# Printing2.net
KiCad netlist of a schematic drawn in Altium Designer
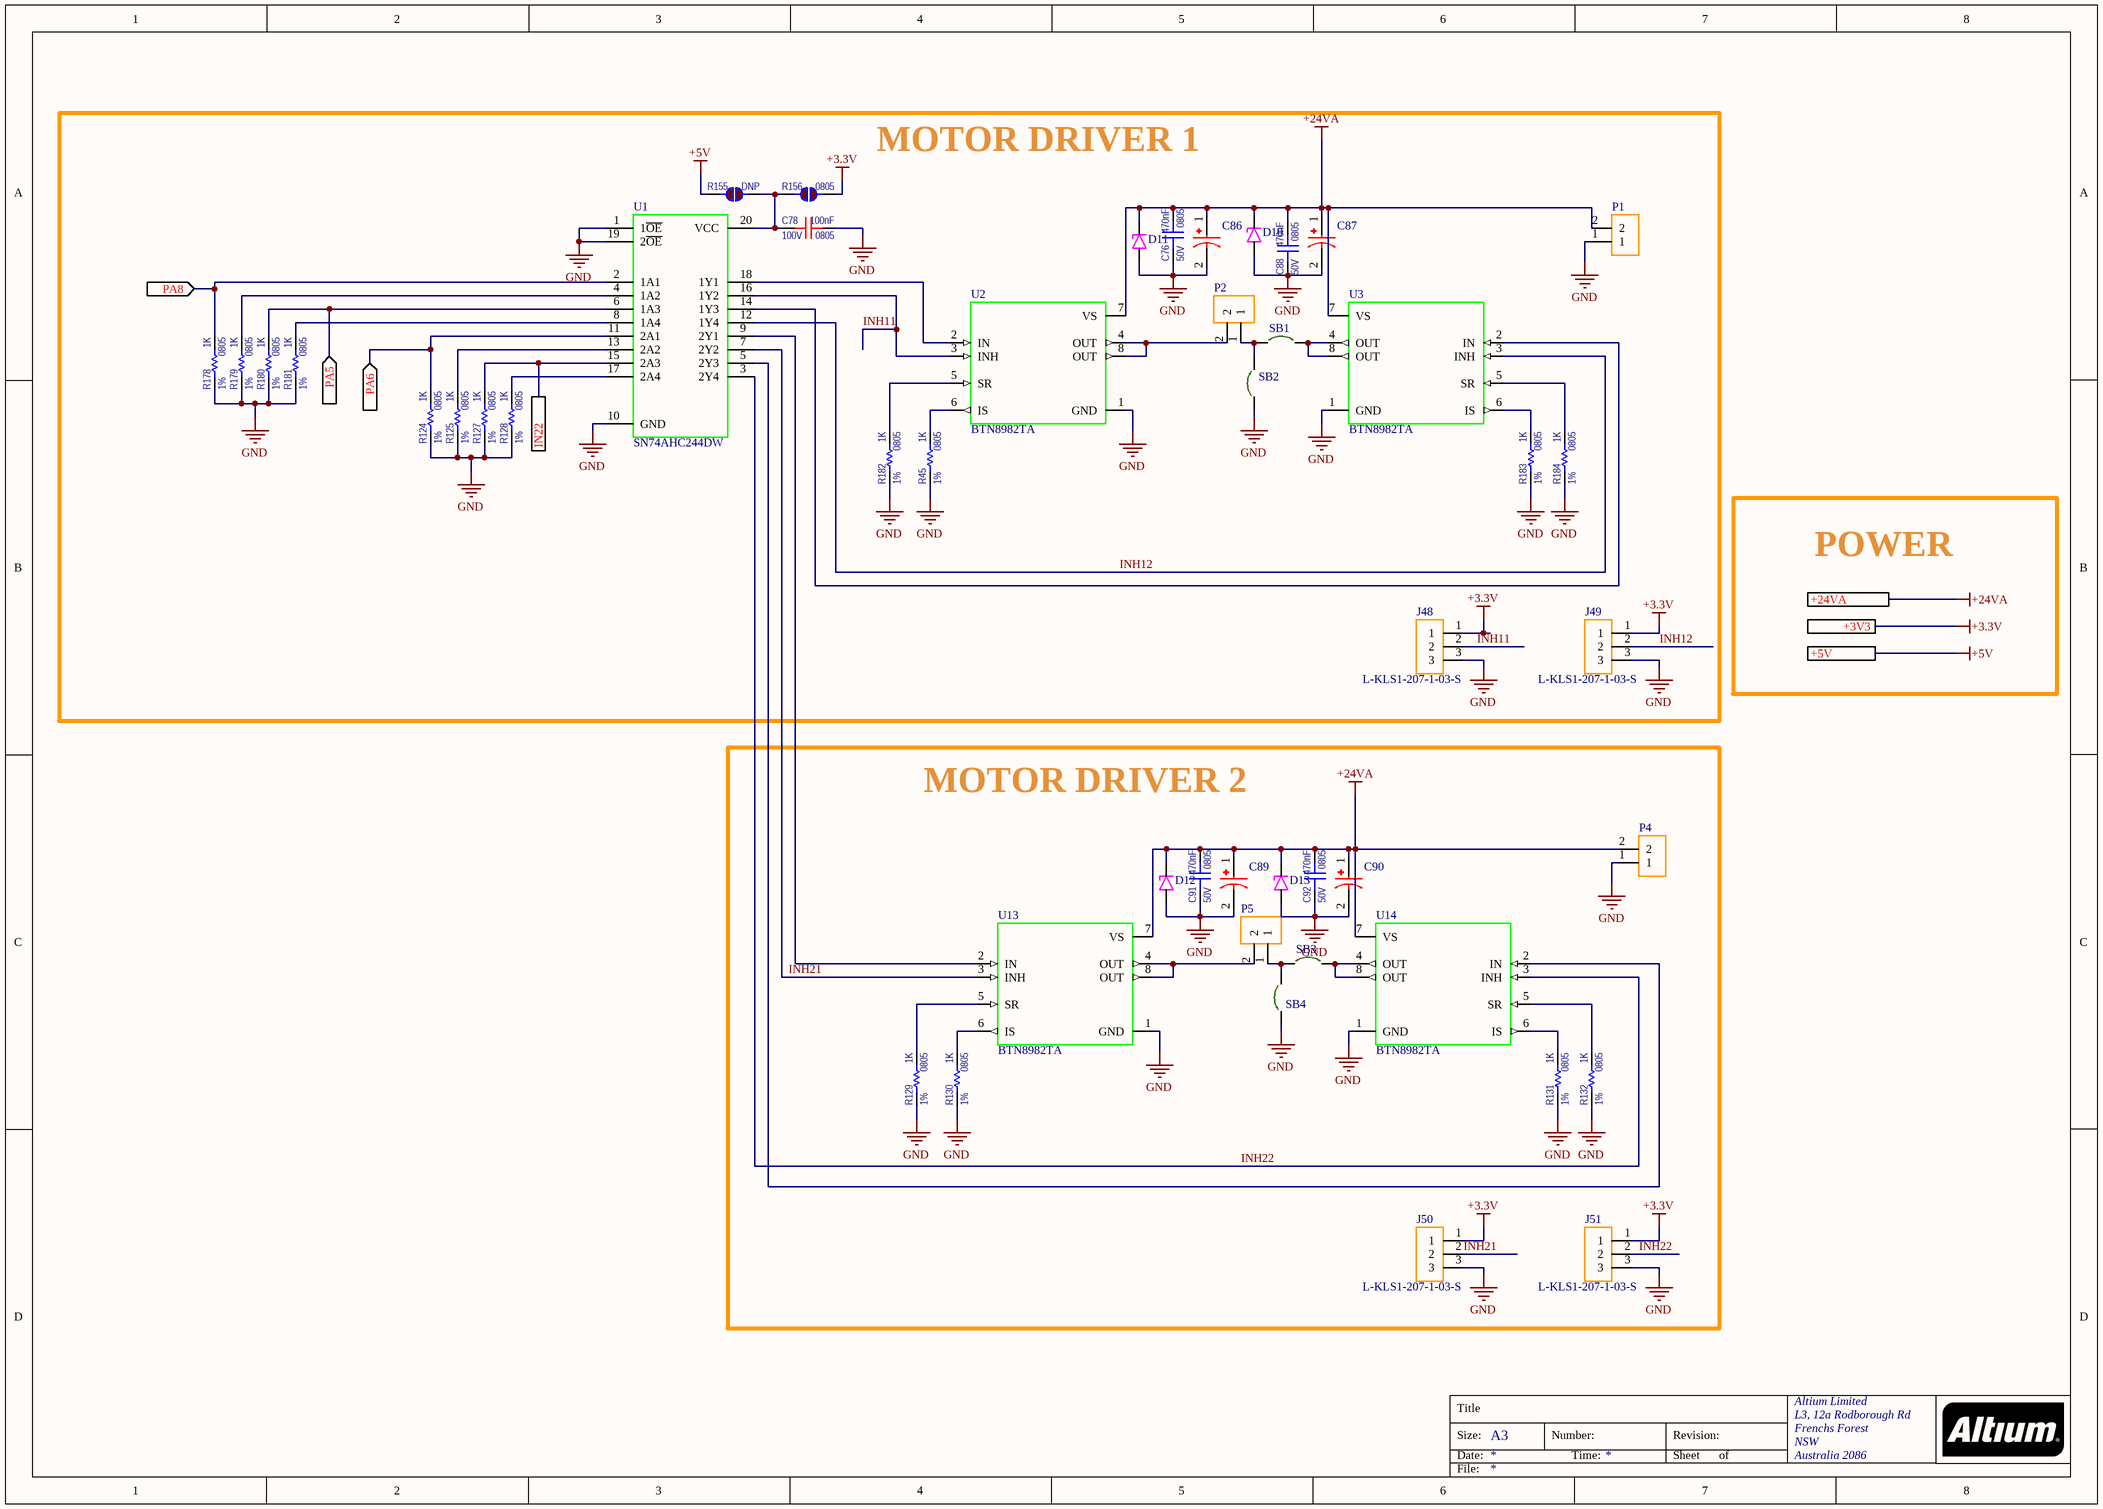
[diagram p0: Printing2.SchDoc]

(export (version "E")
  (design (tool "Eeschema 10.0.6"))
  (components
    (comp (ref "C76")
      (value "470nF")
      (footprint "C_0805_GEN_1.10H")
      (description "CAP_CER_470nF_50V_X7R_10%_0805")
      (fields
        (field (name "VOLTAGE") "50V")
        (field (name "PACKAGE") "0805")
        (field (name "SIMILAR PART") "CL21B474KBFVPNE")
        (field (name "TOLERANCE") "10%")
        (field (name "ADDED BY") "SonerI")
        (field (name "CHECKED BY") "İlkerU")
      )
      (libsource (lib "FireANTs_HwLibDB") (part "Capacitor"))
    )
    (comp (ref "C78")
      (value "100nF")
      (footprint "C_0805_GEN_1.40H")
      (description "CAP_CER_100nF_100V_X7R_10%_0805")
      (fields
        (field (name "VOLTAGE") "100V")
        (field (name "PACKAGE") "0805")
        (field (name "SIMILAR PART") "C0805C104J1RECAUTO7210; C0805X104J1RECAUTO")
        (field (name "TOLERANCE") "10%")
        (field (name "ADDED BY") "İlhanT")
        (field (name "CHECKED BY") "İlkerU")
      )
      (libsource (lib "FireANTs_HwLibDB") (part "ESDSafeCapacitor"))
    )
    (comp (ref "C86")
      (value "100uF/50V")
      (footprint "SC1V107M6L07KVR")
      (libsource (lib "Printing") (part "SC1V107M6L07KVR"))
    )
    (comp (ref "C87")
      (value "100uF/50V")
      (footprint "SC1V107M6L07KVR")
      (libsource (lib "Printing") (part "SC1V107M6L07KVR"))
    )
    (comp (ref "C88")
      (value "470nF")
      (footprint "C_0805_GEN_1.10H")
      (description "CAP_CER_470nF_50V_X7R_10%_0805")
      (fields
        (field (name "VOLTAGE") "50V")
        (field (name "PACKAGE") "0805")
        (field (name "SIMILAR PART") "CL21B474KBFVPNE")
        (field (name "TOLERANCE") "10%")
        (field (name "ADDED BY") "SonerI")
        (field (name "CHECKED BY") "İlkerU")
      )
      (libsource (lib "FireANTs_HwLibDB") (part "Capacitor"))
    )
    (comp (ref "C89")
      (value "100uF/50V")
      (footprint "SC1V107M6L07KVR")
      (libsource (lib "Printing") (part "SC1V107M6L07KVR"))
    )
    (comp (ref "C90")
      (value "100uF/50V")
      (footprint "SC1V107M6L07KVR")
      (libsource (lib "Printing") (part "SC1V107M6L07KVR"))
    )
    (comp (ref "C91")
      (value "470nF")
      (footprint "C_0805_GEN_1.10H")
      (description "CAP_CER_470nF_50V_X7R_10%_0805")
      (fields
        (field (name "VOLTAGE") "50V")
        (field (name "PACKAGE") "0805")
        (field (name "SIMILAR PART") "CL21B474KBFVPNE")
        (field (name "TOLERANCE") "10%")
        (field (name "ADDED BY") "SonerI")
        (field (name "CHECKED BY") "İlkerU")
      )
      (libsource (lib "FireANTs_HwLibDB") (part "Capacitor"))
    )
    (comp (ref "C92")
      (value "470nF")
      (footprint "C_0805_GEN_1.10H")
      (description "CAP_CER_470nF_50V_X7R_10%_0805")
      (fields
        (field (name "VOLTAGE") "50V")
        (field (name "PACKAGE") "0805")
        (field (name "SIMILAR PART") "CL21B474KBFVPNE")
        (field (name "TOLERANCE") "10%")
        (field (name "ADDED BY") "SonerI")
        (field (name "CHECKED BY") "İlkerU")
      )
      (libsource (lib "FireANTs_HwLibDB") (part "Capacitor"))
    )
    (comp (ref "D10")
      (value "SMBJ30A-E3/52")
      (footprint "S2G_R1_00001")
      (description "TVS DIODE 30VWM 48.4VC SMB")
      (fields (field (name "MANUFACTURER") "Vishay Semiconductors"))
      (libsource (lib "Printing") (part "SMBJ30A-E3/52"))
    )
    (comp (ref "D11")
      (value "SMBJ30A-E3/52")
      (footprint "S2G_R1_00001")
      (description "TVS DIODE 30VWM 48.4VC SMB")
      (fields (field (name "MANUFACTURER") "Vishay Semiconductors"))
      (libsource (lib "Printing") (part "SMBJ30A-E3/52"))
    )
    (comp (ref "D12")
      (value "SMBJ30A-E3/52")
      (footprint "S2G_R1_00001")
      (description "TVS DIODE 30VWM 48.4VC SMB")
      (fields (field (name "MANUFACTURER") "Vishay Semiconductors"))
      (libsource (lib "Printing") (part "SMBJ30A-E3/52"))
    )
    (comp (ref "D13")
      (value "SMBJ30A-E3/52")
      (footprint "S2G_R1_00001")
      (description "TVS DIODE 30VWM 48.4VC SMB")
      (fields (field (name "MANUFACTURER") "Vishay Semiconductors"))
      (libsource (lib "Printing") (part "SMBJ30A-E3/52"))
    )
    (comp (ref "J48")
      (value "L-KLS1-207-1-03-S")
      (footprint "L-KLS1-207-1-03-S")
      (libsource (lib "Printing") (part "L-KLS1-207-1-03-S"))
    )
    (comp (ref "J49")
      (value "L-KLS1-207-1-03-S")
      (footprint "L-KLS1-207-1-03-S")
      (libsource (lib "Printing") (part "L-KLS1-207-1-03-S"))
    )
    (comp (ref "J50")
      (value "L-KLS1-207-1-03-S")
      (footprint "L-KLS1-207-1-03-S")
      (libsource (lib "Printing") (part "L-KLS1-207-1-03-S"))
    )
    (comp (ref "J51")
      (value "L-KLS1-207-1-03-S")
      (footprint "L-KLS1-207-1-03-S")
      (libsource (lib "Printing") (part "L-KLS1-207-1-03-S"))
    )
    (comp (ref "P1")
      (value "5.08 Klemens")
      (footprint "5.08 Klemens")
      (libsource (lib "Printing") (part "5.08 Klemens"))
    )
    (comp (ref "P2")
      (value "5.08 Klemens")
      (footprint "5.08 Klemens")
      (libsource (lib "") (part "5.08 Klemens_1"))
    )
    (comp (ref "P4")
      (value "5.08 Klemens")
      (footprint "5.08 Klemens")
      (libsource (lib "Printing") (part "5.08 Klemens"))
    )
    (comp (ref "P5")
      (value "5.08 Klemens")
      (footprint "5.08 Klemens")
      (libsource (lib "") (part "5.08 Klemens_1"))
    )
    (comp (ref "R45")
      (value "1K")
      (footprint "R_0805_GEN_0.70H")
      (description "RES_STD_1K_0.125W_1%_100ppm_0805")
      (fields
        (field (name "TOLERANCE") "1%")
        (field (name "PACKAGE") "0805")
        (field (name "VOLTAGE") "150V")
        (field (name "Comment") "StandardResistor")
        (field (name "ADDED BY") "SonerI")
        (field (name "CHECKED BY") "YasinY")
      )
      (libsource (lib "FireANTs_HwLibDB") (part "StandardResistor"))
    )
    (comp (ref "R124")
      (value "1K")
      (footprint "R_0805_GEN_0.70H")
      (description "RES_STD_1K_0.125W_1%_100ppm_0805")
      (fields
        (field (name "TOLERANCE") "1%")
        (field (name "PACKAGE") "0805")
        (field (name "VOLTAGE") "150V")
        (field (name "Comment") "StandardResistor")
        (field (name "ADDED BY") "SonerI")
        (field (name "CHECKED BY") "YasinY")
      )
      (libsource (lib "FireANTs_HwLibDB") (part "StandardResistor"))
    )
    (comp (ref "R125")
      (value "1K")
      (footprint "R_0805_GEN_0.70H")
      (description "RES_STD_1K_0.125W_1%_100ppm_0805")
      (fields
        (field (name "TOLERANCE") "1%")
        (field (name "PACKAGE") "0805")
        (field (name "VOLTAGE") "150V")
        (field (name "Comment") "StandardResistor")
        (field (name "ADDED BY") "SonerI")
        (field (name "CHECKED BY") "YasinY")
      )
      (libsource (lib "FireANTs_HwLibDB") (part "StandardResistor"))
    )
    (comp (ref "R127")
      (value "1K")
      (footprint "R_0805_GEN_0.70H")
      (description "RES_STD_1K_0.125W_1%_100ppm_0805")
      (fields
        (field (name "TOLERANCE") "1%")
        (field (name "PACKAGE") "0805")
        (field (name "VOLTAGE") "150V")
        (field (name "Comment") "StandardResistor")
        (field (name "ADDED BY") "SonerI")
        (field (name "CHECKED BY") "YasinY")
      )
      (libsource (lib "FireANTs_HwLibDB") (part "StandardResistor"))
    )
    (comp (ref "R128")
      (value "1K")
      (footprint "R_0805_GEN_0.70H")
      (description "RES_STD_1K_0.125W_1%_100ppm_0805")
      (fields
        (field (name "TOLERANCE") "1%")
        (field (name "PACKAGE") "0805")
        (field (name "VOLTAGE") "150V")
        (field (name "Comment") "StandardResistor")
        (field (name "ADDED BY") "SonerI")
        (field (name "CHECKED BY") "YasinY")
      )
      (libsource (lib "FireANTs_HwLibDB") (part "StandardResistor"))
    )
    (comp (ref "R129")
      (value "1K")
      (footprint "R_0805_GEN_0.70H")
      (description "RES_STD_1K_0.125W_1%_100ppm_0805")
      (fields
        (field (name "TOLERANCE") "1%")
        (field (name "PACKAGE") "0805")
        (field (name "VOLTAGE") "150V")
        (field (name "Comment") "StandardResistor")
        (field (name "ADDED BY") "SonerI")
        (field (name "CHECKED BY") "YasinY")
      )
      (libsource (lib "FireANTs_HwLibDB") (part "StandardResistor"))
    )
    (comp (ref "R130")
      (value "1K")
      (footprint "R_0805_GEN_0.70H")
      (description "RES_STD_1K_0.125W_1%_100ppm_0805")
      (fields
        (field (name "TOLERANCE") "1%")
        (field (name "PACKAGE") "0805")
        (field (name "VOLTAGE") "150V")
        (field (name "Comment") "StandardResistor")
        (field (name "ADDED BY") "SonerI")
        (field (name "CHECKED BY") "YasinY")
      )
      (libsource (lib "FireANTs_HwLibDB") (part "StandardResistor"))
    )
    (comp (ref "R131")
      (value "1K")
      (footprint "R_0805_GEN_0.70H")
      (description "RES_STD_1K_0.125W_1%_100ppm_0805")
      (fields
        (field (name "TOLERANCE") "1%")
        (field (name "PACKAGE") "0805")
        (field (name "VOLTAGE") "150V")
        (field (name "Comment") "StandardResistor")
        (field (name "ADDED BY") "SonerI")
        (field (name "CHECKED BY") "YasinY")
      )
      (libsource (lib "FireANTs_HwLibDB") (part "StandardResistor"))
    )
    (comp (ref "R132")
      (value "1K")
      (footprint "R_0805_GEN_0.70H")
      (description "RES_STD_1K_0.125W_1%_100ppm_0805")
      (fields
        (field (name "TOLERANCE") "1%")
        (field (name "PACKAGE") "0805")
        (field (name "VOLTAGE") "150V")
        (field (name "Comment") "StandardResistor")
        (field (name "ADDED BY") "SonerI")
        (field (name "CHECKED BY") "YasinY")
      )
      (libsource (lib "FireANTs_HwLibDB") (part "StandardResistor"))
    )
    (comp (ref "R155")
      (value "StandardJumper")
      (footprint "R_0805_GEN_0.70H")
      (description "RES_STD_0R_0.125W_0805")
      (fields
        (field (name "PACKAGE") "DNP")
        (field (name "TOLERANCE") "5%")
        (field (name "VOLTAGE") "150V")
        (field (name "ADDED BY") "İlhanT")
        (field (name "CHECKED BY") "YasinY")
      )
      (libsource (lib "FireANTs_HwLibDB") (part "StandardJumper"))
    )
    (comp (ref "R156")
      (value "StandardJumper")
      (footprint "R_0805_GEN_0.70H")
      (description "RES_STD_0R_0.125W_0805")
      (fields
        (field (name "PACKAGE") "0805")
        (field (name "TOLERANCE") "5%")
        (field (name "VOLTAGE") "150V")
        (field (name "ADDED BY") "İlhanT")
        (field (name "CHECKED BY") "YasinY")
      )
      (libsource (lib "FireANTs_HwLibDB") (part "StandardJumper"))
    )
    (comp (ref "R178")
      (value "1K")
      (footprint "R_0805_GEN_0.70H")
      (description "RES_STD_1K_0.125W_1%_100ppm_0805")
      (fields
        (field (name "TOLERANCE") "1%")
        (field (name "PACKAGE") "0805")
        (field (name "VOLTAGE") "150V")
        (field (name "Comment") "StandardResistor")
        (field (name "ADDED BY") "SonerI")
        (field (name "CHECKED BY") "YasinY")
      )
      (libsource (lib "FireANTs_HwLibDB") (part "StandardResistor"))
    )
    (comp (ref "R179")
      (value "1K")
      (footprint "R_0805_GEN_0.70H")
      (description "RES_STD_1K_0.125W_1%_100ppm_0805")
      (fields
        (field (name "TOLERANCE") "1%")
        (field (name "PACKAGE") "0805")
        (field (name "VOLTAGE") "150V")
        (field (name "Comment") "StandardResistor")
        (field (name "ADDED BY") "SonerI")
        (field (name "CHECKED BY") "YasinY")
      )
      (libsource (lib "FireANTs_HwLibDB") (part "StandardResistor"))
    )
    (comp (ref "R180")
      (value "1K")
      (footprint "R_0805_GEN_0.70H")
      (description "RES_STD_1K_0.125W_1%_100ppm_0805")
      (fields
        (field (name "TOLERANCE") "1%")
        (field (name "PACKAGE") "0805")
        (field (name "VOLTAGE") "150V")
        (field (name "Comment") "StandardResistor")
        (field (name "ADDED BY") "SonerI")
        (field (name "CHECKED BY") "YasinY")
      )
      (libsource (lib "FireANTs_HwLibDB") (part "StandardResistor"))
    )
    (comp (ref "R181")
      (value "1K")
      (footprint "R_0805_GEN_0.70H")
      (description "RES_STD_1K_0.125W_1%_100ppm_0805")
      (fields
        (field (name "TOLERANCE") "1%")
        (field (name "PACKAGE") "0805")
        (field (name "VOLTAGE") "150V")
        (field (name "Comment") "StandardResistor")
        (field (name "ADDED BY") "SonerI")
        (field (name "CHECKED BY") "YasinY")
      )
      (libsource (lib "FireANTs_HwLibDB") (part "StandardResistor"))
    )
    (comp (ref "R182")
      (value "1K")
      (footprint "R_0805_GEN_0.70H")
      (description "RES_STD_1K_0.125W_1%_100ppm_0805")
      (fields
        (field (name "TOLERANCE") "1%")
        (field (name "PACKAGE") "0805")
        (field (name "VOLTAGE") "150V")
        (field (name "Comment") "StandardResistor")
        (field (name "ADDED BY") "SonerI")
        (field (name "CHECKED BY") "YasinY")
      )
      (libsource (lib "FireANTs_HwLibDB") (part "StandardResistor"))
    )
    (comp (ref "R183")
      (value "1K")
      (footprint "R_0805_GEN_0.70H")
      (description "RES_STD_1K_0.125W_1%_100ppm_0805")
      (fields
        (field (name "TOLERANCE") "1%")
        (field (name "PACKAGE") "0805")
        (field (name "VOLTAGE") "150V")
        (field (name "Comment") "StandardResistor")
        (field (name "ADDED BY") "SonerI")
        (field (name "CHECKED BY") "YasinY")
      )
      (libsource (lib "FireANTs_HwLibDB") (part "StandardResistor"))
    )
    (comp (ref "R184")
      (value "1K")
      (footprint "R_0805_GEN_0.70H")
      (description "RES_STD_1K_0.125W_1%_100ppm_0805")
      (fields
        (field (name "TOLERANCE") "1%")
        (field (name "PACKAGE") "0805")
        (field (name "VOLTAGE") "150V")
        (field (name "Comment") "StandardResistor")
        (field (name "ADDED BY") "SonerI")
        (field (name "CHECKED BY") "YasinY")
      )
      (libsource (lib "FireANTs_HwLibDB") (part "StandardResistor"))
    )
    (comp (ref "SB1") (value "~") (footprint "0805_SB") (libsource (lib "Printing") (part "0805_SB")))
    (comp (ref "SB2") (value "0805_SB") (footprint "0805_SB") (libsource (lib "Printing") (part "0805_SB")))
    (comp (ref "SB3") (value "~") (footprint "0805_SB") (libsource (lib "Printing") (part "0805_SB")))
    (comp (ref "SB4") (value "~") (footprint "0805_SB") (libsource (lib "Printing") (part "0805_SB")))
    (comp (ref "U1")
      (value "SN74AHC244DW")
      (footprint "SN74AHC244DW")
      (description "Buffer/Line Driver 8-CH Non-Inverting 3-ST CMOS 20-Pin SOIC Tube")
      (fields (field (name "MANUFACTURER") "Texas Instruments"))
      (libsource (lib "Printing") (part "SN74AHC244DW"))
    )
    (comp (ref "U2")
      (value "BTN8982TA")
      (footprint "DPAK127P1500X440-8N")
      (description "Motor / Motion / Ignition Controllers & Drivers TRILITH IC / NOVALITH IC")
      (fields (field (name "MF") "Infineon Technologies"))
      (libsource (lib "") (part "BTN8982TA_1"))
    )
    (comp (ref "U3")
      (value "BTN8982TA")
      (footprint "DPAK127P1500X440-8N")
      (description "Motor / Motion / Ignition Controllers & Drivers TRILITH IC / NOVALITH IC")
      (fields (field (name "MF") "Infineon Technologies"))
      (libsource (lib "Printing") (part "BTN8982TA"))
    )
    (comp (ref "U13")
      (value "BTN8982TA")
      (footprint "DPAK127P1500X440-8N")
      (description "Motor / Motion / Ignition Controllers & Drivers TRILITH IC / NOVALITH IC")
      (fields (field (name "MF") "Infineon Technologies"))
      (libsource (lib "") (part "BTN8982TA_1"))
    )
    (comp (ref "U14")
      (value "BTN8982TA")
      (footprint "DPAK127P1500X440-8N")
      (description "Motor / Motion / Ignition Controllers & Drivers TRILITH IC / NOVALITH IC")
      (fields (field (name "MF") "Infineon Technologies"))
      (libsource (lib "Printing") (part "BTN8982TA"))
    )
  )
  (nets
    (net (code "1") (name "+3.3V") (class "Default")
      (node (ref "J48") (pin "1") (pinfunction "1_1") (pintype "passive"))
      (node (ref "J49") (pin "1") (pinfunction "1_1") (pintype "passive"))
      (node (ref "J50") (pin "1") (pinfunction "1_1") (pintype "passive"))
      (node (ref "J51") (pin "1") (pinfunction "1_1") (pintype "passive"))
      (node (ref "R156") (pin "2") (pinfunction "2_2") (pintype "passive"))
    )
    (net (code "2") (name "+5V") (class "Default")
      (node (ref "R155") (pin "1") (pinfunction "1_1") (pintype "passive"))
    )
    (net (code "3") (name "+24VA") (class "Default")
      (node (ref "C76") (pin "2") (pinfunction "2_2") (pintype "passive"))
      (node (ref "C86") (pin "1") (pinfunction "1_1") (pintype "passive"))
      (node (ref "C87") (pin "1") (pinfunction "1_1") (pintype "passive"))
      (node (ref "C88") (pin "2") (pinfunction "2_2") (pintype "passive"))
      (node (ref "C89") (pin "1") (pinfunction "1_1") (pintype "passive"))
      (node (ref "C90") (pin "1") (pinfunction "1_1") (pintype "passive"))
      (node (ref "C91") (pin "2") (pinfunction "2_2") (pintype "passive"))
      (node (ref "C92") (pin "2") (pinfunction "2_2") (pintype "passive"))
      (node (ref "D10") (pin "K") (pinfunction "K_K") (pintype "passive"))
      (node (ref "D11") (pin "K") (pinfunction "K_K") (pintype "passive"))
      (node (ref "D12") (pin "K") (pinfunction "K_K") (pintype "passive"))
      (node (ref "D13") (pin "K") (pinfunction "K_K") (pintype "passive"))
      (node (ref "P1") (pin "2") (pinfunction "2_2") (pintype "passive"))
      (node (ref "P4") (pin "2") (pinfunction "2_2") (pintype "passive"))
      (node (ref "U13") (pin "7") (pinfunction "VS_7") (pintype "power_in"))
      (node (ref "U14") (pin "7") (pinfunction "VS_7") (pintype "power_in"))
      (node (ref "U2") (pin "7") (pinfunction "VS_7") (pintype "power_in"))
      (node (ref "U3") (pin "7") (pinfunction "VS_7") (pintype "power_in"))
    )
    (net (code "4") (name "/IN22") (class "Default")
      (node (ref "R127") (pin "2") (pinfunction "2_2") (pintype "passive"))
      (node (ref "U1") (pin "15") (pinfunction "2A3_15") (pintype "passive"))
    )
    (net (code "5") (name "/INH11") (class "Default")
      (node (ref "J48") (pin "2") (pinfunction "2_2") (pintype "passive"))
      (node (ref "U1") (pin "16") (pinfunction "1Y2_16") (pintype "passive"))
      (node (ref "U2") (pin "3") (pinfunction "INH_3") (pintype "input"))
    )
    (net (code "6") (name "/INH12") (class "Default")
      (node (ref "J49") (pin "2") (pinfunction "2_2") (pintype "passive"))
      (node (ref "U1") (pin "12") (pinfunction "1Y4_12") (pintype "passive"))
      (node (ref "U3") (pin "3") (pinfunction "INH_3") (pintype "input"))
    )
    (net (code "7") (name "/INH21") (class "Default")
      (node (ref "J50") (pin "2") (pinfunction "2_2") (pintype "passive"))
      (node (ref "U1") (pin "7") (pinfunction "2Y2_7") (pintype "passive"))
      (node (ref "U13") (pin "3") (pinfunction "INH_3") (pintype "input"))
    )
    (net (code "8") (name "/INH22") (class "Default")
      (node (ref "J51") (pin "2") (pinfunction "2_2") (pintype "passive"))
      (node (ref "U1") (pin "3") (pinfunction "2Y4_3") (pintype "passive"))
      (node (ref "U14") (pin "3") (pinfunction "INH_3") (pintype "input"))
    )
    (net (code "9") (name "/PA5") (class "Default")
      (node (ref "R180") (pin "2") (pinfunction "2_2") (pintype "passive"))
      (node (ref "U1") (pin "6") (pinfunction "1A3_6") (pintype "passive"))
    )
    (net (code "10") (name "/PA6") (class "Default")
      (node (ref "R124") (pin "2") (pinfunction "2_2") (pintype "passive"))
      (node (ref "U1") (pin "11") (pinfunction "2A1_11") (pintype "passive"))
    )
    (net (code "11") (name "/PA8") (class "Default")
      (node (ref "R178") (pin "2") (pinfunction "2_2") (pintype "passive"))
      (node (ref "U1") (pin "2") (pinfunction "1A1_2") (pintype "passive"))
    )
    (net (code "12") (name "GND") (class "Default")
      (node (ref "C76") (pin "1") (pinfunction "1_1") (pintype "passive"))
      (node (ref "C78") (pin "2") (pinfunction "2_2") (pintype "passive"))
      (node (ref "C86") (pin "2") (pinfunction "2_2") (pintype "passive"))
      (node (ref "C87") (pin "2") (pinfunction "2_2") (pintype "passive"))
      (node (ref "C88") (pin "1") (pinfunction "1_1") (pintype "passive"))
      (node (ref "C89") (pin "2") (pinfunction "2_2") (pintype "passive"))
      (node (ref "C90") (pin "2") (pinfunction "2_2") (pintype "passive"))
      (node (ref "C91") (pin "1") (pinfunction "1_1") (pintype "passive"))
      (node (ref "C92") (pin "1") (pinfunction "1_1") (pintype "passive"))
      (node (ref "D10") (pin "A") (pinfunction "A_A") (pintype "passive"))
      (node (ref "D11") (pin "A") (pinfunction "A_A") (pintype "passive"))
      (node (ref "D12") (pin "A") (pinfunction "A_A") (pintype "passive"))
      (node (ref "D13") (pin "A") (pinfunction "A_A") (pintype "passive"))
      (node (ref "J48") (pin "3") (pinfunction "3_3") (pintype "passive"))
      (node (ref "J49") (pin "3") (pinfunction "3_3") (pintype "passive"))
      (node (ref "J50") (pin "3") (pinfunction "3_3") (pintype "passive"))
      (node (ref "J51") (pin "3") (pinfunction "3_3") (pintype "passive"))
      (node (ref "P1") (pin "1") (pinfunction "1_1") (pintype "passive"))
      (node (ref "P4") (pin "1") (pinfunction "1_1") (pintype "passive"))
      (node (ref "R124") (pin "1") (pinfunction "1_1") (pintype "passive"))
      (node (ref "R125") (pin "1") (pinfunction "1_1") (pintype "passive"))
      (node (ref "R127") (pin "1") (pinfunction "1_1") (pintype "passive"))
      (node (ref "R128") (pin "1") (pinfunction "1_1") (pintype "passive"))
      (node (ref "R129") (pin "1") (pinfunction "1_1") (pintype "passive"))
      (node (ref "R130") (pin "1") (pinfunction "1_1") (pintype "passive"))
      (node (ref "R131") (pin "1") (pinfunction "1_1") (pintype "passive"))
      (node (ref "R132") (pin "1") (pinfunction "1_1") (pintype "passive"))
      (node (ref "R178") (pin "1") (pinfunction "1_1") (pintype "passive"))
      (node (ref "R179") (pin "1") (pinfunction "1_1") (pintype "passive"))
      (node (ref "R180") (pin "1") (pinfunction "1_1") (pintype "passive"))
      (node (ref "R181") (pin "1") (pinfunction "1_1") (pintype "passive"))
      (node (ref "R182") (pin "1") (pinfunction "1_1") (pintype "passive"))
      (node (ref "R183") (pin "1") (pinfunction "1_1") (pintype "passive"))
      (node (ref "R184") (pin "1") (pinfunction "1_1") (pintype "passive"))
      (node (ref "R45") (pin "1") (pinfunction "1_1") (pintype "passive"))
      (node (ref "SB2") (pin "1") (pinfunction "1_1") (pintype "passive"))
      (node (ref "SB4") (pin "1") (pinfunction "1_1") (pintype "passive"))
      (node (ref "U1") (pin "1") (pinfunction "1~{OE}_1") (pintype "passive"))
      (node (ref "U1") (pin "10") (pinfunction "GND_10") (pintype "passive"))
      (node (ref "U1") (pin "19") (pinfunction "2~{OE}_19") (pintype "passive"))
      (node (ref "U13") (pin "1") (pinfunction "GND_1") (pintype "power_in"))
      (node (ref "U14") (pin "1") (pinfunction "GND_1") (pintype "power_in"))
      (node (ref "U2") (pin "1") (pinfunction "GND_1") (pintype "power_in"))
      (node (ref "U3") (pin "1") (pinfunction "GND_1") (pintype "power_in"))
    )
    (net (code "13") (name "Net-(P2-Pad1)") (class "Default")
      (node (ref "P2") (pin "1") (pinfunction "1_1") (pintype "passive"))
      (node (ref "SB1") (pin "1") (pinfunction "1_1") (pintype "passive"))
      (node (ref "SB2") (pin "2") (pinfunction "2_2") (pintype "passive"))
    )
    (net (code "14") (name "Net-(P2-Pad2)") (class "Default")
      (node (ref "P2") (pin "2") (pinfunction "2_2") (pintype "passive"))
      (node (ref "U2") (pin "4") (pinfunction "OUT_4") (pintype "output"))
      (node (ref "U2") (pin "8") (pinfunction "OUT_8") (pintype "output"))
    )
    (net (code "15") (name "Net-(P5-Pad1)") (class "Default")
      (node (ref "P5") (pin "1") (pinfunction "1_1") (pintype "passive"))
      (node (ref "SB3") (pin "1") (pinfunction "1_1") (pintype "passive"))
      (node (ref "SB4") (pin "2") (pinfunction "2_2") (pintype "passive"))
    )
    (net (code "16") (name "Net-(P5-Pad2)") (class "Default")
      (node (ref "P5") (pin "2") (pinfunction "2_2") (pintype "passive"))
      (node (ref "U13") (pin "4") (pinfunction "OUT_4") (pintype "output"))
      (node (ref "U13") (pin "8") (pinfunction "OUT_8") (pintype "output"))
    )
    (net (code "17") (name "Net-(SB1-Pad2)") (class "Default")
      (node (ref "SB1") (pin "2") (pinfunction "2_2") (pintype "passive"))
      (node (ref "U3") (pin "4") (pinfunction "OUT_4") (pintype "output"))
      (node (ref "U3") (pin "8") (pinfunction "OUT_8") (pintype "output"))
    )
    (net (code "18") (name "Net-(SB3-Pad2)") (class "Default")
      (node (ref "SB3") (pin "2") (pinfunction "2_2") (pintype "passive"))
      (node (ref "U14") (pin "4") (pinfunction "OUT_4") (pintype "output"))
      (node (ref "U14") (pin "8") (pinfunction "OUT_8") (pintype "output"))
    )
    (net (code "19") (name "Net-(U1-1A2)") (class "Default")
      (node (ref "R179") (pin "2") (pinfunction "2_2") (pintype "passive"))
      (node (ref "U1") (pin "4") (pinfunction "1A2_4") (pintype "passive"))
    )
    (net (code "20") (name "Net-(U1-1A4)") (class "Default")
      (node (ref "R181") (pin "2") (pinfunction "2_2") (pintype "passive"))
      (node (ref "U1") (pin "8") (pinfunction "1A4_8") (pintype "passive"))
    )
    (net (code "21") (name "Net-(U1-1Y1)") (class "Default")
      (node (ref "U1") (pin "18") (pinfunction "1Y1_18") (pintype "passive"))
      (node (ref "U2") (pin "2") (pinfunction "IN_2") (pintype "input"))
    )
    (net (code "22") (name "Net-(U1-1Y3)") (class "Default")
      (node (ref "U1") (pin "14") (pinfunction "1Y3_14") (pintype "passive"))
      (node (ref "U3") (pin "2") (pinfunction "IN_2") (pintype "input"))
    )
    (net (code "23") (name "Net-(U1-2A2)") (class "Default")
      (node (ref "R125") (pin "2") (pinfunction "2_2") (pintype "passive"))
      (node (ref "U1") (pin "13") (pinfunction "2A2_13") (pintype "passive"))
    )
    (net (code "24") (name "Net-(U1-2A4)") (class "Default")
      (node (ref "R128") (pin "2") (pinfunction "2_2") (pintype "passive"))
      (node (ref "U1") (pin "17") (pinfunction "2A4_17") (pintype "passive"))
    )
    (net (code "25") (name "Net-(U1-2Y1)") (class "Default")
      (node (ref "U1") (pin "9") (pinfunction "2Y1_9") (pintype "passive"))
      (node (ref "U13") (pin "2") (pinfunction "IN_2") (pintype "input"))
    )
    (net (code "26") (name "Net-(U1-2Y3)") (class "Default")
      (node (ref "U1") (pin "5") (pinfunction "2Y3_5") (pintype "passive"))
      (node (ref "U14") (pin "2") (pinfunction "IN_2") (pintype "input"))
    )
    (net (code "27") (name "Net-(U1-VCC)") (class "Default")
      (node (ref "C78") (pin "1") (pinfunction "1_1") (pintype "passive"))
      (node (ref "R155") (pin "2") (pinfunction "2_2") (pintype "passive"))
      (node (ref "R156") (pin "1") (pinfunction "1_1") (pintype "passive"))
      (node (ref "U1") (pin "20") (pinfunction "VCC_20") (pintype "passive"))
    )
    (net (code "28") (name "Net-(U2-IS)") (class "Default")
      (node (ref "R45") (pin "2") (pinfunction "2_2") (pintype "passive"))
      (node (ref "U2") (pin "6") (pinfunction "IS_6") (pintype "output"))
    )
    (net (code "29") (name "Net-(U2-SR)") (class "Default")
      (node (ref "R182") (pin "2") (pinfunction "2_2") (pintype "passive"))
      (node (ref "U2") (pin "5") (pinfunction "SR_5") (pintype "input"))
    )
    (net (code "30") (name "Net-(U3-IS)") (class "Default")
      (node (ref "R183") (pin "2") (pinfunction "2_2") (pintype "passive"))
      (node (ref "U3") (pin "6") (pinfunction "IS_6") (pintype "output"))
    )
    (net (code "31") (name "Net-(U3-SR)") (class "Default")
      (node (ref "R184") (pin "2") (pinfunction "2_2") (pintype "passive"))
      (node (ref "U3") (pin "5") (pinfunction "SR_5") (pintype "input"))
    )
    (net (code "32") (name "Net-(U13-IS)") (class "Default")
      (node (ref "R130") (pin "2") (pinfunction "2_2") (pintype "passive"))
      (node (ref "U13") (pin "6") (pinfunction "IS_6") (pintype "output"))
    )
    (net (code "33") (name "Net-(U13-SR)") (class "Default")
      (node (ref "R129") (pin "2") (pinfunction "2_2") (pintype "passive"))
      (node (ref "U13") (pin "5") (pinfunction "SR_5") (pintype "input"))
    )
    (net (code "34") (name "Net-(U14-IS)") (class "Default")
      (node (ref "R131") (pin "2") (pinfunction "2_2") (pintype "passive"))
      (node (ref "U14") (pin "6") (pinfunction "IS_6") (pintype "output"))
    )
    (net (code "35") (name "Net-(U14-SR)") (class "Default")
      (node (ref "R132") (pin "2") (pinfunction "2_2") (pintype "passive"))
      (node (ref "U14") (pin "5") (pinfunction "SR_5") (pintype "input"))
    )
  )
)
